# 3MIC_ximpedanceREVB.net
KiCad netlist of a schematic drawn in EAGLE
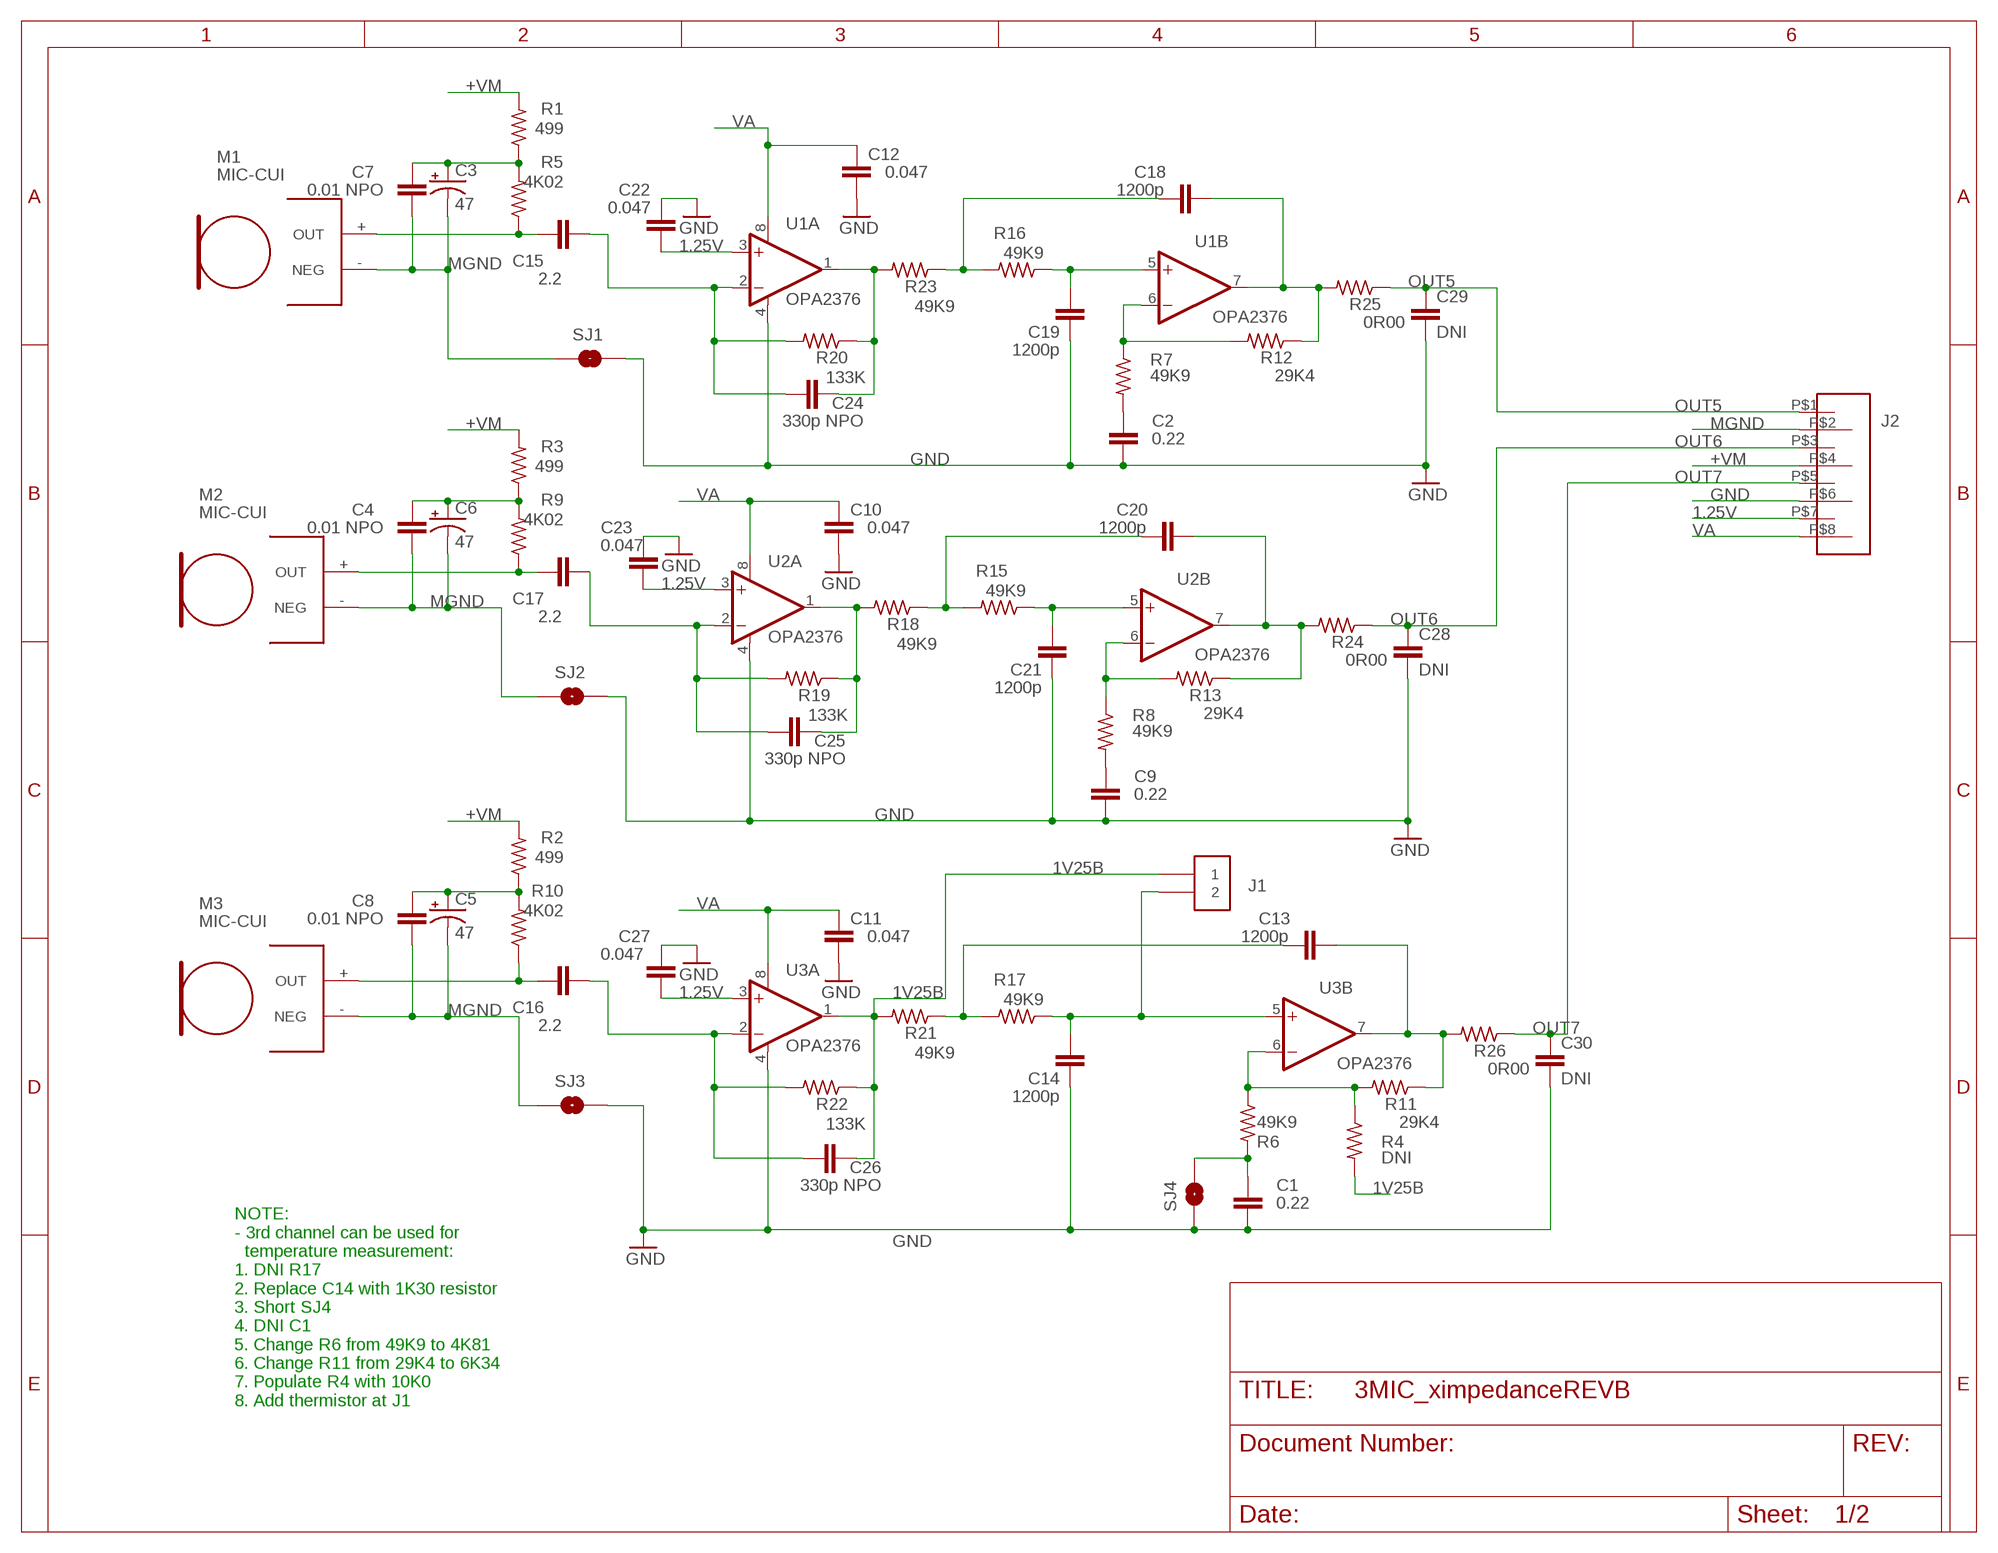
[diagram p0: schematic, sheet 1]

(export (version "E")
  (design (tool "Eeschema 10.0.6"))
  (components
    (comp (ref "C1")
      (value "0.22")
      (footprint "eagle-import:1206S")
      (libsource (lib "eagle-import") (part "CAPS1206S"))
    )
    (comp (ref "C2")
      (value "0.22")
      (footprint "eagle-import:1206S")
      (libsource (lib "eagle-import") (part "CAPS1206S"))
    )
    (comp (ref "C3")
      (value "47")
      (footprint "eagle-import:EIA3216")
      (libsource (lib "eagle-import") (part "CAP_POL1206"))
    )
    (comp (ref "C4")
      (value "0.01 NPO")
      (footprint "eagle-import:0603S")
      (libsource (lib "eagle-import") (part "CAPS0603S"))
    )
    (comp (ref "C5")
      (value "47")
      (footprint "eagle-import:EIA3216")
      (libsource (lib "eagle-import") (part "CAP_POL1206"))
    )
    (comp (ref "C6")
      (value "47")
      (footprint "eagle-import:EIA3216")
      (libsource (lib "eagle-import") (part "CAP_POL1206"))
    )
    (comp (ref "C7")
      (value "0.01 NPO")
      (footprint "eagle-import:0603S")
      (libsource (lib "eagle-import") (part "CAPS0603S"))
    )
    (comp (ref "C8")
      (value "0.01 NPO")
      (footprint "eagle-import:0603S")
      (libsource (lib "eagle-import") (part "CAPS0603S"))
    )
    (comp (ref "C9")
      (value "0.22")
      (footprint "eagle-import:1206S")
      (libsource (lib "eagle-import") (part "CAPS1206S"))
    )
    (comp (ref "C10")
      (value "0.047")
      (footprint "eagle-import:0805S")
      (libsource (lib "eagle-import") (part "CAPS0805S"))
    )
    (comp (ref "C11")
      (value "0.047")
      (footprint "eagle-import:0805S")
      (libsource (lib "eagle-import") (part "CAPS0805S"))
    )
    (comp (ref "C12")
      (value "0.047")
      (footprint "eagle-import:0805S")
      (libsource (lib "eagle-import") (part "CAPS0805S"))
    )
    (comp (ref "C13")
      (value "1200p")
      (footprint "eagle-import:1206S")
      (libsource (lib "eagle-import") (part "CAPS1206S"))
    )
    (comp (ref "C14")
      (value "1200p")
      (footprint "eagle-import:1206S")
      (libsource (lib "eagle-import") (part "CAPS1206S"))
    )
    (comp (ref "C15")
      (value "2.2")
      (footprint "eagle-import:1210S")
      (libsource (lib "eagle-import") (part "CAPS1210S"))
    )
    (comp (ref "C16")
      (value "2.2")
      (footprint "eagle-import:1210S")
      (libsource (lib "eagle-import") (part "CAPS1210S"))
    )
    (comp (ref "C17")
      (value "2.2")
      (footprint "eagle-import:1210S")
      (libsource (lib "eagle-import") (part "CAPS1210S"))
    )
    (comp (ref "C18")
      (value "1200p")
      (footprint "eagle-import:1206S")
      (libsource (lib "eagle-import") (part "CAPS1206S"))
    )
    (comp (ref "C19")
      (value "1200p")
      (footprint "eagle-import:1206S")
      (libsource (lib "eagle-import") (part "CAPS1206S"))
    )
    (comp (ref "C20")
      (value "1200p")
      (footprint "eagle-import:1206S")
      (libsource (lib "eagle-import") (part "CAPS1206S"))
    )
    (comp (ref "C21")
      (value "1200p")
      (footprint "eagle-import:1206S")
      (libsource (lib "eagle-import") (part "CAPS1206S"))
    )
    (comp (ref "C22")
      (value "0.047")
      (footprint "eagle-import:0805S")
      (libsource (lib "eagle-import") (part "CAPS0805S"))
    )
    (comp (ref "C23")
      (value "0.047")
      (footprint "eagle-import:0805S")
      (libsource (lib "eagle-import") (part "CAPS0805S"))
    )
    (comp (ref "C24")
      (value "330p NPO")
      (footprint "eagle-import:0805S")
      (libsource (lib "eagle-import") (part "CAPS0805S"))
    )
    (comp (ref "C25")
      (value "330p NPO")
      (footprint "eagle-import:0805S")
      (libsource (lib "eagle-import") (part "CAPS0805S"))
    )
    (comp (ref "C26")
      (value "330p NPO")
      (footprint "eagle-import:0805S")
      (libsource (lib "eagle-import") (part "CAPS0805S"))
    )
    (comp (ref "C27")
      (value "0.047")
      (footprint "eagle-import:0805S")
      (libsource (lib "eagle-import") (part "CAPS0805S"))
    )
    (comp (ref "C28")
      (value "DNI")
      (footprint "eagle-import:0603S")
      (libsource (lib "eagle-import") (part "CAPS0603S"))
    )
    (comp (ref "C29")
      (value "DNI")
      (footprint "eagle-import:0603S")
      (libsource (lib "eagle-import") (part "CAPS0603S"))
    )
    (comp (ref "C30")
      (value "DNI")
      (footprint "eagle-import:0603S")
      (libsource (lib "eagle-import") (part "CAPS0603S"))
    )
    (comp (ref "J1")
      (value "CON2TIP-BOT-PADS")
      (footprint "eagle-import:TOP-BOT-PADS")
      (libsource (lib "eagle-import") (part "CON2TIP-BOT-PADS"))
    )
    (comp (ref "J2")
      (value "CON8")
      (footprint "eagle-import:CON8-EDGE")
      (libsource (lib "eagle-import") (part "CON8"))
    )
    (comp (ref "M1")
      (value "MIC-CUI")
      (footprint "eagle-import:CUI_EDGE")
      (libsource (lib "eagle-import") (part "MIC-CUI"))
    )
    (comp (ref "M2")
      (value "MIC-CUI")
      (footprint "eagle-import:CUI_EDGE")
      (libsource (lib "eagle-import") (part "MIC-CUI"))
    )
    (comp (ref "M3")
      (value "MIC-CUI")
      (footprint "eagle-import:CUI_EDGE")
      (libsource (lib "eagle-import") (part "MIC-CUI"))
    )
    (comp (ref "R1")
      (value "499")
      (footprint "eagle-import:0603S")
      (libsource (lib "eagle-import") (part "RESISTOR_SM0603S"))
    )
    (comp (ref "R2")
      (value "499")
      (footprint "eagle-import:0603S")
      (libsource (lib "eagle-import") (part "RESISTOR_SM0603S"))
    )
    (comp (ref "R3")
      (value "499")
      (footprint "eagle-import:0603S")
      (libsource (lib "eagle-import") (part "RESISTOR_SM0603S"))
    )
    (comp (ref "R4")
      (value "DNI")
      (footprint "eagle-import:0603S")
      (libsource (lib "eagle-import") (part "RESISTOR_SM0603S"))
    )
    (comp (ref "R5")
      (value "4K02")
      (footprint "eagle-import:0603S")
      (libsource (lib "eagle-import") (part "RESISTOR_SM0603S"))
    )
    (comp (ref "R6")
      (value "49K9")
      (footprint "eagle-import:0603S")
      (libsource (lib "eagle-import") (part "RESISTOR_SM0603S"))
    )
    (comp (ref "R7")
      (value "49K9")
      (footprint "eagle-import:0603S")
      (libsource (lib "eagle-import") (part "RESISTOR_SM0603S"))
    )
    (comp (ref "R8")
      (value "49K9")
      (footprint "eagle-import:0603S")
      (libsource (lib "eagle-import") (part "RESISTOR_SM0603S"))
    )
    (comp (ref "R9")
      (value "4K02")
      (footprint "eagle-import:0603S")
      (libsource (lib "eagle-import") (part "RESISTOR_SM0603S"))
    )
    (comp (ref "R10")
      (value "4K02")
      (footprint "eagle-import:0603S")
      (libsource (lib "eagle-import") (part "RESISTOR_SM0603S"))
    )
    (comp (ref "R11")
      (value "29K4")
      (footprint "eagle-import:0603S")
      (libsource (lib "eagle-import") (part "RESISTOR_SM0603S"))
    )
    (comp (ref "R12")
      (value "29K4")
      (footprint "eagle-import:0603S")
      (libsource (lib "eagle-import") (part "RESISTOR_SM0603S"))
    )
    (comp (ref "R13")
      (value "29K4")
      (footprint "eagle-import:0603S")
      (libsource (lib "eagle-import") (part "RESISTOR_SM0603S"))
    )
    (comp (ref "R15")
      (value "49K9")
      (footprint "eagle-import:0603S")
      (libsource (lib "eagle-import") (part "RESISTOR_SM0603S"))
    )
    (comp (ref "R16")
      (value "49K9")
      (footprint "eagle-import:0603S")
      (libsource (lib "eagle-import") (part "RESISTOR_SM0603S"))
    )
    (comp (ref "R17")
      (value "49K9")
      (footprint "eagle-import:0603S")
      (libsource (lib "eagle-import") (part "RESISTOR_SM0603S"))
    )
    (comp (ref "R18")
      (value "49K9")
      (footprint "eagle-import:0603S")
      (libsource (lib "eagle-import") (part "RESISTOR_SM0603S"))
    )
    (comp (ref "R19")
      (value "133K")
      (footprint "eagle-import:0603S")
      (libsource (lib "eagle-import") (part "RESISTOR_SM0603S"))
    )
    (comp (ref "R20")
      (value "133K")
      (footprint "eagle-import:0603S")
      (libsource (lib "eagle-import") (part "RESISTOR_SM0603S"))
    )
    (comp (ref "R21")
      (value "49K9")
      (footprint "eagle-import:0603S")
      (libsource (lib "eagle-import") (part "RESISTOR_SM0603S"))
    )
    (comp (ref "R22")
      (value "133K")
      (footprint "eagle-import:0603S")
      (libsource (lib "eagle-import") (part "RESISTOR_SM0603S"))
    )
    (comp (ref "R23")
      (value "49K9")
      (footprint "eagle-import:0603S")
      (libsource (lib "eagle-import") (part "RESISTOR_SM0603S"))
    )
    (comp (ref "R24")
      (value "0R00")
      (footprint "eagle-import:0603S")
      (libsource (lib "eagle-import") (part "RESISTOR_SM0603S"))
    )
    (comp (ref "R25")
      (value "0R00")
      (footprint "eagle-import:0603S")
      (libsource (lib "eagle-import") (part "RESISTOR_SM0603S"))
    )
    (comp (ref "R26")
      (value "0R00")
      (footprint "eagle-import:0603S")
      (libsource (lib "eagle-import") (part "RESISTOR_SM0603S"))
    )
    (comp (ref "SJ1")
      (value "SOLDERJUMPERTRACE")
      (footprint "eagle-import:SJ_2S-TRACE")
      (libsource (lib "eagle-import") (part "SOLDERJUMPERTRACE"))
    )
    (comp (ref "SJ2")
      (value "SOLDERJUMPERTRACE")
      (footprint "eagle-import:SJ_2S-TRACE")
      (libsource (lib "eagle-import") (part "SOLDERJUMPERTRACE"))
    )
    (comp (ref "SJ3")
      (value "SOLDERJUMPERTRACE")
      (footprint "eagle-import:SJ_2S-TRACE")
      (libsource (lib "eagle-import") (part "SOLDERJUMPERTRACE"))
    )
    (comp (ref "SJ4")
      (value "SOLDERJUMPERNO")
      (footprint "eagle-import:SJ_2S-NO")
      (libsource (lib "eagle-import") (part "jfrc_SOLDERJUMPERNO"))
    )
    (comp (ref "U1")
      (value "OPA2376")
      (footprint "eagle-import:MSOP08")
      (fields (field (name "MF") "TEXAS INSTRUMENTS") (field (name "MPN") "OPA2237EA/250"))
      (libsource (lib "eagle-import") (part "OPA2237E"))
    )
    (comp (ref "U2")
      (value "OPA2376")
      (footprint "eagle-import:MSOP08")
      (fields (field (name "MF") "TEXAS INSTRUMENTS") (field (name "MPN") "OPA2237EA/250"))
      (libsource (lib "eagle-import") (part "OPA2237E"))
    )
    (comp (ref "U3")
      (value "OPA2376")
      (footprint "eagle-import:MSOP08")
      (fields (field (name "MF") "TEXAS INSTRUMENTS") (field (name "MPN") "OPA2237EA/250"))
      (libsource (lib "eagle-import") (part "OPA2237E"))
    )
  )
  (nets
    (net (code "1") (name "+VM") (class "Default")
      (node (ref "J2") (pin "P$4") (pinfunction "4_P$4") (pintype "bidirectional"))
      (node (ref "R1") (pin "2") (pinfunction "2_2") (pintype "passive"))
      (node (ref "R2") (pin "2") (pinfunction "2_2") (pintype "passive"))
      (node (ref "R3") (pin "2") (pinfunction "2_2") (pintype "passive"))
    )
    (net (code "2") (name "1.25V") (class "Default")
      (node (ref "C22") (pin "2") (pinfunction "2_2") (pintype "passive"))
      (node (ref "C23") (pin "2") (pinfunction "2_2") (pintype "passive"))
      (node (ref "C27") (pin "2") (pinfunction "2_2") (pintype "passive"))
      (node (ref "J2") (pin "P$7") (pinfunction "7_P$7") (pintype "bidirectional"))
      (node (ref "U1") (pin "3") (pinfunction "+IN_3") (pintype "input"))
      (node (ref "U2") (pin "3") (pinfunction "+IN_3") (pintype "input"))
      (node (ref "U3") (pin "3") (pinfunction "+IN_3") (pintype "input"))
    )
    (net (code "3") (name "1V25B") (class "Default")
      (node (ref "C26") (pin "1") (pinfunction "1_1") (pintype "passive"))
      (node (ref "J1") (pin "1") (pinfunction "1_1") (pintype "bidirectional"))
      (node (ref "R21") (pin "2") (pinfunction "2_2") (pintype "passive"))
      (node (ref "R22") (pin "1") (pinfunction "1_1") (pintype "passive"))
      (node (ref "R4") (pin "2") (pinfunction "2_2") (pintype "passive"))
      (node (ref "U3") (pin "1") (pinfunction "OUT_1") (pintype "output"))
    )
    (net (code "4") (name "GND") (class "Default")
      (node (ref "C1") (pin "1") (pinfunction "1_1") (pintype "passive"))
      (node (ref "C10") (pin "1") (pinfunction "1_1") (pintype "passive"))
      (node (ref "C11") (pin "1") (pinfunction "1_1") (pintype "passive"))
      (node (ref "C12") (pin "1") (pinfunction "1_1") (pintype "passive"))
      (node (ref "C14") (pin "1") (pinfunction "1_1") (pintype "passive"))
      (node (ref "C19") (pin "1") (pinfunction "1_1") (pintype "passive"))
      (node (ref "C2") (pin "1") (pinfunction "1_1") (pintype "passive"))
      (node (ref "C21") (pin "1") (pinfunction "1_1") (pintype "passive"))
      (node (ref "C22") (pin "1") (pinfunction "1_1") (pintype "passive"))
      (node (ref "C23") (pin "1") (pinfunction "1_1") (pintype "passive"))
      (node (ref "C27") (pin "1") (pinfunction "1_1") (pintype "passive"))
      (node (ref "C28") (pin "2") (pinfunction "2_2") (pintype "passive"))
      (node (ref "C29") (pin "2") (pinfunction "2_2") (pintype "passive"))
      (node (ref "C30") (pin "2") (pinfunction "2_2") (pintype "passive"))
      (node (ref "C9") (pin "1") (pinfunction "1_1") (pintype "passive"))
      (node (ref "J2") (pin "P$6") (pinfunction "6_P$6") (pintype "bidirectional"))
      (node (ref "SJ1") (pin "2") (pinfunction "2_2") (pintype "passive"))
      (node (ref "SJ2") (pin "2") (pinfunction "2_2") (pintype "passive"))
      (node (ref "SJ3") (pin "2") (pinfunction "2_2") (pintype "passive"))
      (node (ref "SJ4") (pin "1") (pinfunction "1_1") (pintype "passive"))
      (node (ref "U1") (pin "4") (pinfunction "V-_4") (pintype "power_in"))
      (node (ref "U2") (pin "4") (pinfunction "V-_4") (pintype "power_in"))
      (node (ref "U3") (pin "4") (pinfunction "V-_4") (pintype "power_in"))
    )
    (net (code "5") (name "MGND") (class "Default")
      (node (ref "C3") (pin "C") (pinfunction "-_C") (pintype "passive"))
      (node (ref "C4") (pin "2") (pinfunction "2_2") (pintype "passive"))
      (node (ref "C5") (pin "C") (pinfunction "-_C") (pintype "passive"))
      (node (ref "C6") (pin "C") (pinfunction "-_C") (pintype "passive"))
      (node (ref "C7") (pin "2") (pinfunction "2_2") (pintype "passive"))
      (node (ref "C8") (pin "2") (pinfunction "2_2") (pintype "passive"))
      (node (ref "J2") (pin "P$2") (pinfunction "2_P$2") (pintype "bidirectional"))
      (node (ref "M1") (pin "-") (pinfunction "NEG_-") (pintype "bidirectional"))
      (node (ref "M2") (pin "-") (pinfunction "NEG_-") (pintype "bidirectional"))
      (node (ref "M3") (pin "-") (pinfunction "NEG_-") (pintype "bidirectional"))
      (node (ref "SJ1") (pin "1") (pinfunction "1_1") (pintype "passive"))
      (node (ref "SJ2") (pin "1") (pinfunction "1_1") (pintype "passive"))
      (node (ref "SJ3") (pin "1") (pinfunction "1_1") (pintype "passive"))
    )
    (net (code "6") (name "Net-(C1-Pad2)") (class "Default")
      (node (ref "C1") (pin "2") (pinfunction "2_2") (pintype "passive"))
      (node (ref "R6") (pin "2") (pinfunction "2_2") (pintype "passive"))
      (node (ref "SJ4") (pin "2") (pinfunction "2_2") (pintype "passive"))
    )
    (net (code "7") (name "Net-(C2-Pad2)") (class "Default")
      (node (ref "C2") (pin "2") (pinfunction "2_2") (pintype "passive"))
      (node (ref "R7") (pin "2") (pinfunction "2_2") (pintype "passive"))
    )
    (net (code "8") (name "Net-(C3-+)") (class "Default")
      (node (ref "C3") (pin "A") (pinfunction "+_A") (pintype "passive"))
      (node (ref "C7") (pin "1") (pinfunction "1_1") (pintype "passive"))
      (node (ref "R1") (pin "1") (pinfunction "1_1") (pintype "passive"))
      (node (ref "R5") (pin "2") (pinfunction "2_2") (pintype "passive"))
    )
    (net (code "9") (name "Net-(C5-+)") (class "Default")
      (node (ref "C5") (pin "A") (pinfunction "+_A") (pintype "passive"))
      (node (ref "C8") (pin "1") (pinfunction "1_1") (pintype "passive"))
      (node (ref "R10") (pin "2") (pinfunction "2_2") (pintype "passive"))
      (node (ref "R2") (pin "1") (pinfunction "1_1") (pintype "passive"))
    )
    (net (code "10") (name "Net-(C6-+)") (class "Default")
      (node (ref "C4") (pin "1") (pinfunction "1_1") (pintype "passive"))
      (node (ref "C6") (pin "A") (pinfunction "+_A") (pintype "passive"))
      (node (ref "R3") (pin "1") (pinfunction "1_1") (pintype "passive"))
      (node (ref "R9") (pin "2") (pinfunction "2_2") (pintype "passive"))
    )
    (net (code "11") (name "Net-(C9-Pad2)") (class "Default")
      (node (ref "C9") (pin "2") (pinfunction "2_2") (pintype "passive"))
      (node (ref "R8") (pin "2") (pinfunction "2_2") (pintype "passive"))
    )
    (net (code "12") (name "Net-(C13-Pad2)") (class "Default")
      (node (ref "C13") (pin "2") (pinfunction "2_2") (pintype "passive"))
      (node (ref "R17") (pin "2") (pinfunction "2_2") (pintype "passive"))
      (node (ref "R21") (pin "1") (pinfunction "1_1") (pintype "passive"))
    )
    (net (code "13") (name "Net-(C18-Pad2)") (class "Default")
      (node (ref "C18") (pin "2") (pinfunction "2_2") (pintype "passive"))
      (node (ref "R16") (pin "2") (pinfunction "2_2") (pintype "passive"))
      (node (ref "R23") (pin "1") (pinfunction "1_1") (pintype "passive"))
    )
    (net (code "14") (name "Net-(C20-Pad2)") (class "Default")
      (node (ref "C20") (pin "2") (pinfunction "2_2") (pintype "passive"))
      (node (ref "R15") (pin "2") (pinfunction "2_2") (pintype "passive"))
      (node (ref "R18") (pin "1") (pinfunction "1_1") (pintype "passive"))
    )
    (net (code "15") (name "Net-(M1-OUT)") (class "Default")
      (node (ref "C15") (pin "1") (pinfunction "1_1") (pintype "passive"))
      (node (ref "M1") (pin "+") (pinfunction "OUT_+") (pintype "bidirectional"))
      (node (ref "R5") (pin "1") (pinfunction "1_1") (pintype "passive"))
    )
    (net (code "16") (name "Net-(M2-OUT)") (class "Default")
      (node (ref "C17") (pin "1") (pinfunction "1_1") (pintype "passive"))
      (node (ref "M2") (pin "+") (pinfunction "OUT_+") (pintype "bidirectional"))
      (node (ref "R9") (pin "1") (pinfunction "1_1") (pintype "passive"))
    )
    (net (code "17") (name "Net-(M3-OUT)") (class "Default")
      (node (ref "C16") (pin "1") (pinfunction "1_1") (pintype "passive"))
      (node (ref "M3") (pin "+") (pinfunction "OUT_+") (pintype "bidirectional"))
      (node (ref "R10") (pin "1") (pinfunction "1_1") (pintype "passive"))
    )
    (net (code "18") (name "Net-(U1A--IN)") (class "Default")
      (node (ref "C15") (pin "2") (pinfunction "2_2") (pintype "passive"))
      (node (ref "C24") (pin "2") (pinfunction "2_2") (pintype "passive"))
      (node (ref "R20") (pin "2") (pinfunction "2_2") (pintype "passive"))
      (node (ref "U1") (pin "2") (pinfunction "-IN_2") (pintype "input"))
    )
    (net (code "19") (name "Net-(U1A-OUT)") (class "Default")
      (node (ref "C24") (pin "1") (pinfunction "1_1") (pintype "passive"))
      (node (ref "R20") (pin "1") (pinfunction "1_1") (pintype "passive"))
      (node (ref "R23") (pin "2") (pinfunction "2_2") (pintype "passive"))
      (node (ref "U1") (pin "1") (pinfunction "OUT_1") (pintype "output"))
    )
    (net (code "20") (name "Net-(U1B-+IN)") (class "Default")
      (node (ref "C19") (pin "2") (pinfunction "2_2") (pintype "passive"))
      (node (ref "R16") (pin "1") (pinfunction "1_1") (pintype "passive"))
      (node (ref "U1") (pin "5") (pinfunction "+IN_5") (pintype "input"))
    )
    (net (code "21") (name "Net-(U1B--IN)") (class "Default")
      (node (ref "R12") (pin "2") (pinfunction "2_2") (pintype "passive"))
      (node (ref "R7") (pin "1") (pinfunction "1_1") (pintype "passive"))
      (node (ref "U1") (pin "6") (pinfunction "-IN_6") (pintype "input"))
    )
    (net (code "22") (name "Net-(U1B-OUT)") (class "Default")
      (node (ref "C18") (pin "1") (pinfunction "1_1") (pintype "passive"))
      (node (ref "R12") (pin "1") (pinfunction "1_1") (pintype "passive"))
      (node (ref "R25") (pin "2") (pinfunction "2_2") (pintype "passive"))
      (node (ref "U1") (pin "7") (pinfunction "OUT_7") (pintype "output"))
    )
    (net (code "23") (name "Net-(U2A--IN)") (class "Default")
      (node (ref "C17") (pin "2") (pinfunction "2_2") (pintype "passive"))
      (node (ref "C25") (pin "2") (pinfunction "2_2") (pintype "passive"))
      (node (ref "R19") (pin "2") (pinfunction "2_2") (pintype "passive"))
      (node (ref "U2") (pin "2") (pinfunction "-IN_2") (pintype "input"))
    )
    (net (code "24") (name "Net-(U2A-OUT)") (class "Default")
      (node (ref "C25") (pin "1") (pinfunction "1_1") (pintype "passive"))
      (node (ref "R18") (pin "2") (pinfunction "2_2") (pintype "passive"))
      (node (ref "R19") (pin "1") (pinfunction "1_1") (pintype "passive"))
      (node (ref "U2") (pin "1") (pinfunction "OUT_1") (pintype "output"))
    )
    (net (code "25") (name "Net-(U2B-+IN)") (class "Default")
      (node (ref "C21") (pin "2") (pinfunction "2_2") (pintype "passive"))
      (node (ref "R15") (pin "1") (pinfunction "1_1") (pintype "passive"))
      (node (ref "U2") (pin "5") (pinfunction "+IN_5") (pintype "input"))
    )
    (net (code "26") (name "Net-(U2B--IN)") (class "Default")
      (node (ref "R13") (pin "2") (pinfunction "2_2") (pintype "passive"))
      (node (ref "R8") (pin "1") (pinfunction "1_1") (pintype "passive"))
      (node (ref "U2") (pin "6") (pinfunction "-IN_6") (pintype "input"))
    )
    (net (code "27") (name "Net-(U2B-OUT)") (class "Default")
      (node (ref "C20") (pin "1") (pinfunction "1_1") (pintype "passive"))
      (node (ref "R13") (pin "1") (pinfunction "1_1") (pintype "passive"))
      (node (ref "R24") (pin "2") (pinfunction "2_2") (pintype "passive"))
      (node (ref "U2") (pin "7") (pinfunction "OUT_7") (pintype "output"))
    )
    (net (code "28") (name "Net-(U3A--IN)") (class "Default")
      (node (ref "C16") (pin "2") (pinfunction "2_2") (pintype "passive"))
      (node (ref "C26") (pin "2") (pinfunction "2_2") (pintype "passive"))
      (node (ref "R22") (pin "2") (pinfunction "2_2") (pintype "passive"))
      (node (ref "U3") (pin "2") (pinfunction "-IN_2") (pintype "input"))
    )
    (net (code "29") (name "Net-(U3B-+IN)") (class "Default")
      (node (ref "C14") (pin "2") (pinfunction "2_2") (pintype "passive"))
      (node (ref "J1") (pin "2") (pinfunction "2_2") (pintype "bidirectional"))
      (node (ref "R17") (pin "1") (pinfunction "1_1") (pintype "passive"))
      (node (ref "U3") (pin "5") (pinfunction "+IN_5") (pintype "input"))
    )
    (net (code "30") (name "Net-(U3B--IN)") (class "Default")
      (node (ref "R11") (pin "2") (pinfunction "2_2") (pintype "passive"))
      (node (ref "R4") (pin "1") (pinfunction "1_1") (pintype "passive"))
      (node (ref "R6") (pin "1") (pinfunction "1_1") (pintype "passive"))
      (node (ref "U3") (pin "6") (pinfunction "-IN_6") (pintype "input"))
    )
    (net (code "31") (name "Net-(U3B-OUT)") (class "Default")
      (node (ref "C13") (pin "1") (pinfunction "1_1") (pintype "passive"))
      (node (ref "R11") (pin "1") (pinfunction "1_1") (pintype "passive"))
      (node (ref "R26") (pin "2") (pinfunction "2_2") (pintype "passive"))
      (node (ref "U3") (pin "7") (pinfunction "OUT_7") (pintype "output"))
    )
    (net (code "32") (name "OUT5") (class "Default")
      (node (ref "C29") (pin "1") (pinfunction "1_1") (pintype "passive"))
      (node (ref "J2") (pin "P$1") (pinfunction "1_P$1") (pintype "bidirectional"))
      (node (ref "R25") (pin "1") (pinfunction "1_1") (pintype "passive"))
    )
    (net (code "33") (name "OUT6") (class "Default")
      (node (ref "C28") (pin "1") (pinfunction "1_1") (pintype "passive"))
      (node (ref "J2") (pin "P$3") (pinfunction "3_P$3") (pintype "bidirectional"))
      (node (ref "R24") (pin "1") (pinfunction "1_1") (pintype "passive"))
    )
    (net (code "34") (name "OUT7") (class "Default")
      (node (ref "C30") (pin "1") (pinfunction "1_1") (pintype "passive"))
      (node (ref "J2") (pin "P$5") (pinfunction "5_P$5") (pintype "bidirectional"))
      (node (ref "R26") (pin "1") (pinfunction "1_1") (pintype "passive"))
    )
    (net (code "35") (name "VA") (class "Default")
      (node (ref "C10") (pin "2") (pinfunction "2_2") (pintype "passive"))
      (node (ref "C11") (pin "2") (pinfunction "2_2") (pintype "passive"))
      (node (ref "C12") (pin "2") (pinfunction "2_2") (pintype "passive"))
      (node (ref "J2") (pin "P$8") (pinfunction "8_P$8") (pintype "bidirectional"))
      (node (ref "U1") (pin "8") (pinfunction "V+_8") (pintype "power_in"))
      (node (ref "U2") (pin "8") (pinfunction "V+_8") (pintype "power_in"))
      (node (ref "U3") (pin "8") (pinfunction "V+_8") (pintype "power_in"))
    )
  )
)
